# taster.net
KiCad netlist of a schematic drawn in EAGLE
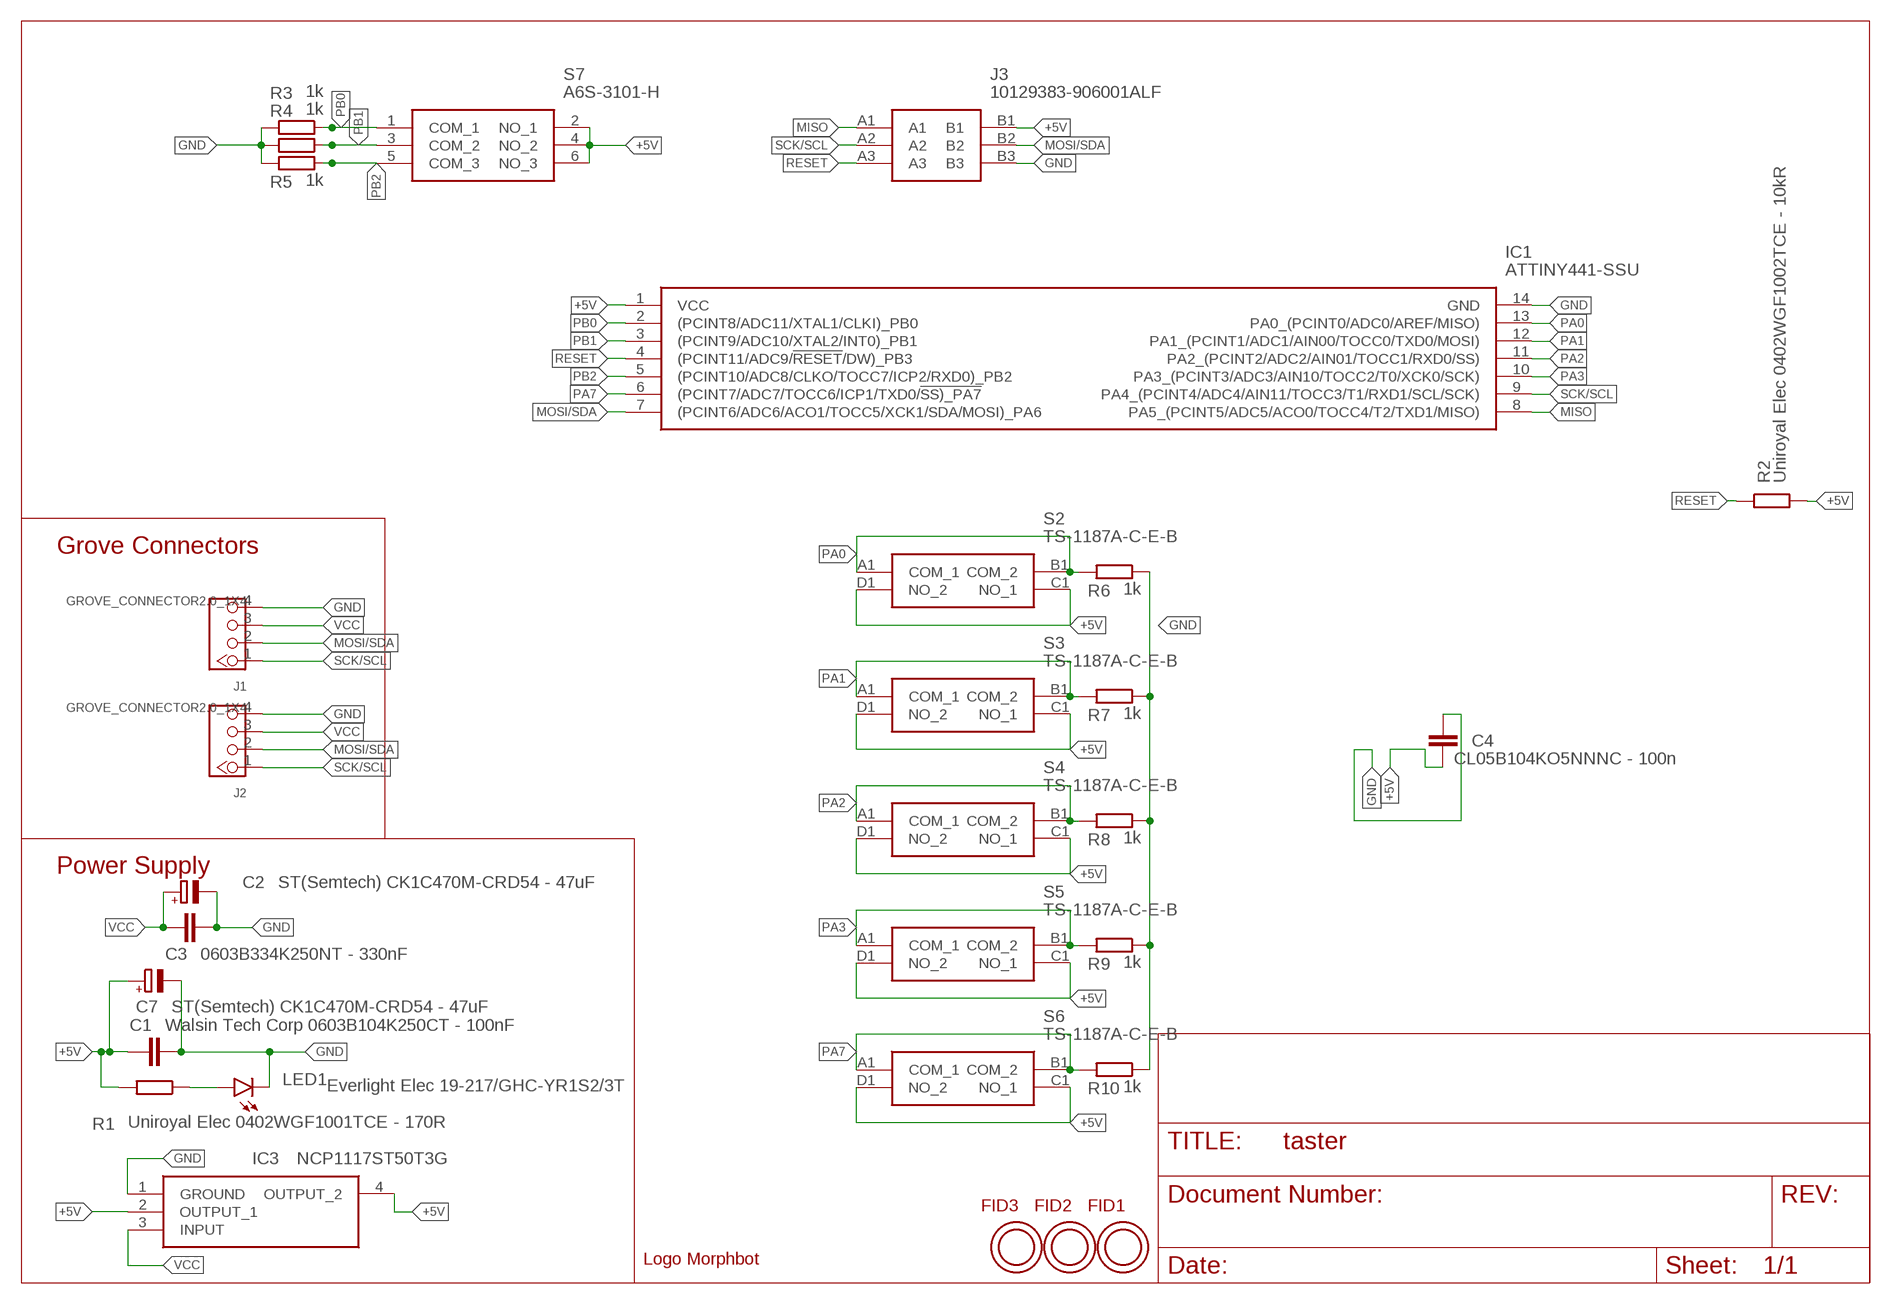
[diagram p0: schematic, sheet 1]

(export (version "E")
  (design (tool "Eeschema 10.0.6"))
  (components
    (comp (ref "C1")
      (value "Walsin Tech Corp 0603B104K250CT - 100nF")
      (footprint "eagle-import:C0603")
      (libsource (lib "eagle-import") (part "C-EUC0603"))
    )
    (comp (ref "C2")
      (value "ST(Semtech) CK1C470M-CRD54 - 47uF")
      (footprint "eagle-import:PANASONIC_C")
      (libsource (lib "eagle-import") (part "CPOL-EUC"))
    )
    (comp (ref "C3")
      (value "0603B334K250NT - 330nF")
      (footprint "eagle-import:C0603")
      (libsource (lib "eagle-import") (part "C-EUC0603"))
    )
    (comp (ref "C4")
      (value "CL05B104KO5NNNC - 100n")
      (footprint "eagle-import:C0402")
      (libsource (lib "eagle-import") (part "C-EUC0402"))
    )
    (comp (ref "C7")
      (value "ST(Semtech) CK1C470M-CRD54 - 47uF")
      (footprint "eagle-import:PANASONIC_C")
      (libsource (lib "eagle-import") (part "CPOL-EUC"))
    )
    (comp (ref "FID1")
      (value "OPEN-PNP-FIDUCIAL")
      (footprint "eagle-import:OPEN-PNP-FIDUCIAL")
      (libsource (lib "eagle-import") (part "OPEN-PNP-FIDUCIAL"))
    )
    (comp (ref "FID2")
      (value "OPEN-PNP-FIDUCIAL")
      (footprint "eagle-import:OPEN-PNP-FIDUCIAL")
      (libsource (lib "eagle-import") (part "OPEN-PNP-FIDUCIAL"))
    )
    (comp (ref "FID3")
      (value "OPEN-PNP-FIDUCIAL")
      (footprint "eagle-import:OPEN-PNP-FIDUCIAL")
      (libsource (lib "eagle-import") (part "OPEN-PNP-FIDUCIAL"))
    )
    (comp (ref "IC1")
      (value "ATTINY441-SSU")
      (footprint "eagle-import:SOIC127P600X175-14N")
      (fields (field (name "MOUSER_PART_NUMBER") "556-ATTINY441-SSU"))
      (libsource (lib "eagle-import") (part "ATTINY441-SSU"))
    )
    (comp (ref "IC3")
      (value "NCP1117ST50T3G")
      (footprint "eagle-import:SOT230P700X180-4N")
      (fields (field (name "MOUSER_PART_NUMBER") "863-NCP1117ST50T3G"))
      (libsource (lib "eagle-import") (part "NCP1117ST50T3G"))
    )
    (comp (ref "J1")
      (value "GROVE_CONNECTOR2.0_1X4")
      (footprint "eagle-import:2.0_1X4_STRAIGHT")
      (libsource (lib "eagle-import") (part "GROVE_CONNECTOR2.0_1X4"))
    )
    (comp (ref "J2")
      (value "GROVE_CONNECTOR2.0_1X4")
      (footprint "eagle-import:2.0_1X4_STRAIGHT")
      (libsource (lib "eagle-import") (part "GROVE_CONNECTOR2.0_1X4"))
    )
    (comp (ref "J3")
      (value "10129383-906001ALF")
      (footprint "eagle-import:10129383906001ALF")
      (fields (field (name "MOUSER_PART_NUMBER") "649-1012938390601ALF"))
      (libsource (lib "eagle-import") (part "10129383-906001ALF"))
    )
    (comp (ref "LED1")
      (value "Everlight Elec 19-217/GHC-YR1S2/3T")
      (footprint "eagle-import:CHIPLED_0603")
      (libsource (lib "eagle-import") (part "LEDCHIPLED_0603"))
    )
    (comp (ref "R1")
      (value "Uniroyal Elec 0402WGF1001TCE - 170R")
      (footprint "eagle-import:R0402")
      (libsource (lib "eagle-import") (part "R-EU_R0402"))
    )
    (comp (ref "R2")
      (value "Uniroyal Elec 0402WGF1002TCE - 10kR")
      (footprint "eagle-import:R0402")
      (libsource (lib "eagle-import") (part "R-EU_R0402"))
    )
    (comp (ref "R3")
      (value "1k")
      (footprint "eagle-import:R0402")
      (libsource (lib "eagle-import") (part "R-EU_R0402"))
    )
    (comp (ref "R4")
      (value "1k")
      (footprint "eagle-import:R0402")
      (libsource (lib "eagle-import") (part "R-EU_R0402"))
    )
    (comp (ref "R5")
      (value "1k")
      (footprint "eagle-import:R0402")
      (libsource (lib "eagle-import") (part "R-EU_R0402"))
    )
    (comp (ref "R6")
      (value "1k")
      (footprint "eagle-import:R0402")
      (libsource (lib "eagle-import") (part "R-EU_R0402"))
    )
    (comp (ref "R7")
      (value "1k")
      (footprint "eagle-import:R0402")
      (libsource (lib "eagle-import") (part "R-EU_R0402"))
    )
    (comp (ref "R8")
      (value "1k")
      (footprint "eagle-import:R0402")
      (libsource (lib "eagle-import") (part "R-EU_R0402"))
    )
    (comp (ref "R9")
      (value "1k")
      (footprint "eagle-import:R0402")
      (libsource (lib "eagle-import") (part "R-EU_R0402"))
    )
    (comp (ref "R10")
      (value "1k")
      (footprint "eagle-import:R0402")
      (libsource (lib "eagle-import") (part "R-EU_R0402"))
    )
    (comp (ref "S2")
      (value "TS-1187A-C-E-B")
      (footprint "eagle-import:TS1187ACEB")
      (fields (field (name "MOUSER_PART_NUMBER") "611-PTS526SK15SMR2L"))
      (libsource (lib "eagle-import") (part "TS-1187A-C-E-B"))
    )
    (comp (ref "S3")
      (value "TS-1187A-C-E-B")
      (footprint "eagle-import:TS1187ACEB")
      (fields (field (name "MOUSER_PART_NUMBER") "611-PTS526SK15SMR2L"))
      (libsource (lib "eagle-import") (part "TS-1187A-C-E-B"))
    )
    (comp (ref "S4")
      (value "TS-1187A-C-E-B")
      (footprint "eagle-import:TS1187ACEB")
      (fields (field (name "MOUSER_PART_NUMBER") "611-PTS526SK15SMR2L"))
      (libsource (lib "eagle-import") (part "TS-1187A-C-E-B"))
    )
    (comp (ref "S5")
      (value "TS-1187A-C-E-B")
      (footprint "eagle-import:TS1187ACEB")
      (fields (field (name "MOUSER_PART_NUMBER") "611-PTS526SK15SMR2L"))
      (libsource (lib "eagle-import") (part "TS-1187A-C-E-B"))
    )
    (comp (ref "S6")
      (value "TS-1187A-C-E-B")
      (footprint "eagle-import:TS1187ACEB")
      (fields (field (name "MOUSER_PART_NUMBER") "611-PTS526SK15SMR2L"))
      (libsource (lib "eagle-import") (part "TS-1187A-C-E-B"))
    )
    (comp (ref "S7")
      (value "A6S-3101-H")
      (footprint "eagle-import:A6S3104H")
      (fields (field (name "MOUSER_PART_NUMBER") "653-A6S-3101-H"))
      (libsource (lib "eagle-import") (part "A6S-3101-H"))
    )
    (comp (ref "U$1")
      (value "LOGO_MORPHBOT5MM")
      (footprint "eagle-import:LOGO_MORPHBOT")
      (libsource (lib "eagle-import") (part "LOGO_MORPHBOT5MM"))
    )
  )
  (nets
    (net (code "1") (name "+5V") (class "Default")
      (node (ref "C1") (pin "1") (pinfunction "1_1") (pintype "passive"))
      (node (ref "C4") (pin "1") (pinfunction "1_1") (pintype "passive"))
      (node (ref "C7") (pin "+") (pinfunction "+_+") (pintype "passive"))
      (node (ref "IC1") (pin "1") (pinfunction "VCC_1") (pintype "bidirectional"))
      (node (ref "IC3") (pin "2") (pinfunction "OUTPUT_1_2") (pintype "bidirectional"))
      (node (ref "IC3") (pin "4") (pinfunction "OUTPUT_2_4") (pintype "bidirectional"))
      (node (ref "J3") (pin "B1") (pinfunction "B1_B1") (pintype "bidirectional"))
      (node (ref "R1") (pin "2") (pinfunction "2_2") (pintype "passive"))
      (node (ref "R2") (pin "2") (pinfunction "2_2") (pintype "passive"))
      (node (ref "S2") (pin "C1") (pinfunction "NO_1_C1") (pintype "bidirectional"))
      (node (ref "S2") (pin "D1") (pinfunction "NO_2_D1") (pintype "bidirectional"))
      (node (ref "S3") (pin "C1") (pinfunction "NO_1_C1") (pintype "bidirectional"))
      (node (ref "S3") (pin "D1") (pinfunction "NO_2_D1") (pintype "bidirectional"))
      (node (ref "S4") (pin "C1") (pinfunction "NO_1_C1") (pintype "bidirectional"))
      (node (ref "S4") (pin "D1") (pinfunction "NO_2_D1") (pintype "bidirectional"))
      (node (ref "S5") (pin "C1") (pinfunction "NO_1_C1") (pintype "bidirectional"))
      (node (ref "S5") (pin "D1") (pinfunction "NO_2_D1") (pintype "bidirectional"))
      (node (ref "S6") (pin "C1") (pinfunction "NO_1_C1") (pintype "bidirectional"))
      (node (ref "S6") (pin "D1") (pinfunction "NO_2_D1") (pintype "bidirectional"))
      (node (ref "S7") (pin "2") (pinfunction "NO_1_2") (pintype "bidirectional"))
      (node (ref "S7") (pin "4") (pinfunction "NO_2_4") (pintype "bidirectional"))
      (node (ref "S7") (pin "6") (pinfunction "NO_3_6") (pintype "bidirectional"))
    )
    (net (code "2") (name "GND") (class "Default")
      (node (ref "C1") (pin "2") (pinfunction "2_2") (pintype "passive"))
      (node (ref "C2") (pin "-") (pinfunction "-_-") (pintype "passive"))
      (node (ref "C3") (pin "1") (pinfunction "1_1") (pintype "passive"))
      (node (ref "C4") (pin "2") (pinfunction "2_2") (pintype "passive"))
      (node (ref "C7") (pin "-") (pinfunction "-_-") (pintype "passive"))
      (node (ref "IC1") (pin "14") (pinfunction "GND_14") (pintype "bidirectional"))
      (node (ref "IC3") (pin "1") (pinfunction "GROUND_1") (pintype "bidirectional"))
      (node (ref "J1") (pin "4") (pinfunction "4_4") (pintype "bidirectional"))
      (node (ref "J2") (pin "4") (pinfunction "4_4") (pintype "bidirectional"))
      (node (ref "J3") (pin "B3") (pinfunction "B3_B3") (pintype "bidirectional"))
      (node (ref "LED1") (pin "C") (pinfunction "C_C") (pintype "passive"))
      (node (ref "R10") (pin "1") (pinfunction "1_1") (pintype "passive"))
      (node (ref "R3") (pin "2") (pinfunction "2_2") (pintype "passive"))
      (node (ref "R4") (pin "2") (pinfunction "2_2") (pintype "passive"))
      (node (ref "R5") (pin "2") (pinfunction "2_2") (pintype "passive"))
      (node (ref "R6") (pin "1") (pinfunction "1_1") (pintype "passive"))
      (node (ref "R7") (pin "1") (pinfunction "1_1") (pintype "passive"))
      (node (ref "R8") (pin "1") (pinfunction "1_1") (pintype "passive"))
      (node (ref "R9") (pin "1") (pinfunction "1_1") (pintype "passive"))
    )
    (net (code "3") (name "MISO") (class "Default")
      (node (ref "IC1") (pin "8") (pinfunction "PA5_(PCINT5/ADC5/ACO0/TOCC4/T2/TXD1/MISO)_8") (pintype "bidirectional"))
      (node (ref "J3") (pin "A1") (pinfunction "A1_A1") (pintype "bidirectional"))
    )
    (net (code "4") (name "MOSI{slash}SDA") (class "Default")
      (node (ref "IC1") (pin "7") (pinfunction "(PCINT6/ADC6/ACO1/TOCC5/XCK1/SDA/MOSI)_PA6_7") (pintype "bidirectional"))
      (node (ref "J1") (pin "2") (pinfunction "2_2") (pintype "bidirectional"))
      (node (ref "J2") (pin "2") (pinfunction "2_2") (pintype "bidirectional"))
      (node (ref "J3") (pin "B2") (pinfunction "B2_B2") (pintype "bidirectional"))
    )
    (net (code "5") (name "Net-(LED1-PadA)") (class "Default")
      (node (ref "LED1") (pin "A") (pinfunction "A_A") (pintype "passive"))
      (node (ref "R1") (pin "1") (pinfunction "1_1") (pintype "passive"))
    )
    (net (code "6") (name "PA0") (class "Default")
      (node (ref "IC1") (pin "13") (pinfunction "PA0_(PCINT0/ADC0/AREF/MISO)_13") (pintype "bidirectional"))
      (node (ref "R6") (pin "2") (pinfunction "2_2") (pintype "passive"))
      (node (ref "S2") (pin "A1") (pinfunction "COM_1_A1") (pintype "bidirectional"))
      (node (ref "S2") (pin "B1") (pinfunction "COM_2_B1") (pintype "bidirectional"))
    )
    (net (code "7") (name "PA1") (class "Default")
      (node (ref "IC1") (pin "12") (pinfunction "PA1_(PCINT1/ADC1/AIN00/TOCC0/TXD0/MOSI)_12") (pintype "bidirectional"))
      (node (ref "R7") (pin "2") (pinfunction "2_2") (pintype "passive"))
      (node (ref "S3") (pin "A1") (pinfunction "COM_1_A1") (pintype "bidirectional"))
      (node (ref "S3") (pin "B1") (pinfunction "COM_2_B1") (pintype "bidirectional"))
    )
    (net (code "8") (name "PA2") (class "Default")
      (node (ref "IC1") (pin "11") (pinfunction "PA2_(PCINT2/ADC2/AIN01/TOCC1/RXD0/SS)_11") (pintype "bidirectional"))
      (node (ref "R8") (pin "2") (pinfunction "2_2") (pintype "passive"))
      (node (ref "S4") (pin "A1") (pinfunction "COM_1_A1") (pintype "bidirectional"))
      (node (ref "S4") (pin "B1") (pinfunction "COM_2_B1") (pintype "bidirectional"))
    )
    (net (code "9") (name "PA3") (class "Default")
      (node (ref "IC1") (pin "10") (pinfunction "PA3_(PCINT3/ADC3/AIN10/TOCC2/T0/XCK0/SCK)_10") (pintype "bidirectional"))
      (node (ref "R9") (pin "2") (pinfunction "2_2") (pintype "passive"))
      (node (ref "S5") (pin "A1") (pinfunction "COM_1_A1") (pintype "bidirectional"))
      (node (ref "S5") (pin "B1") (pinfunction "COM_2_B1") (pintype "bidirectional"))
    )
    (net (code "10") (name "PA7") (class "Default")
      (node (ref "IC1") (pin "6") (pinfunction "(PCINT7/ADC7/TOCC6/ICP1/TXD0/~{SS})_PA7_6") (pintype "bidirectional"))
      (node (ref "R10") (pin "2") (pinfunction "2_2") (pintype "passive"))
      (node (ref "S6") (pin "A1") (pinfunction "COM_1_A1") (pintype "bidirectional"))
      (node (ref "S6") (pin "B1") (pinfunction "COM_2_B1") (pintype "bidirectional"))
    )
    (net (code "11") (name "PB0") (class "Default")
      (node (ref "IC1") (pin "2") (pinfunction "(PCINT8/ADC11/XTAL1/CLKI)_PB0_2") (pintype "bidirectional"))
      (node (ref "R3") (pin "1") (pinfunction "1_1") (pintype "passive"))
      (node (ref "S7") (pin "1") (pinfunction "COM_1_1") (pintype "bidirectional"))
    )
    (net (code "12") (name "PB1") (class "Default")
      (node (ref "IC1") (pin "3") (pinfunction "(PCINT9/ADC10/XTAL2/INT0)_PB1_3") (pintype "bidirectional"))
      (node (ref "R4") (pin "1") (pinfunction "1_1") (pintype "passive"))
      (node (ref "S7") (pin "3") (pinfunction "COM_2_3") (pintype "bidirectional"))
    )
    (net (code "13") (name "PB2") (class "Default")
      (node (ref "IC1") (pin "5") (pinfunction "(PCINT10/ADC8/CLKO/TOCC7/ICP2/RXD0)_PB2_5") (pintype "bidirectional"))
      (node (ref "R5") (pin "1") (pinfunction "1_1") (pintype "passive"))
      (node (ref "S7") (pin "5") (pinfunction "COM_3_5") (pintype "bidirectional"))
    )
    (net (code "14") (name "RESET") (class "Default")
      (node (ref "IC1") (pin "4") (pinfunction "(PCINT11/ADC9/~{RESET}/DW)_PB3_4") (pintype "bidirectional"))
      (node (ref "J3") (pin "A3") (pinfunction "A3_A3") (pintype "bidirectional"))
      (node (ref "R2") (pin "1") (pinfunction "1_1") (pintype "passive"))
    )
    (net (code "15") (name "SCK{slash}SCL") (class "Default")
      (node (ref "IC1") (pin "9") (pinfunction "PA4_(PCINT4/ADC4/AIN11/TOCC3/T1/RXD1/SCL/SCK)_9") (pintype "bidirectional"))
      (node (ref "J1") (pin "1") (pinfunction "1_1") (pintype "bidirectional"))
      (node (ref "J2") (pin "1") (pinfunction "1_1") (pintype "bidirectional"))
      (node (ref "J3") (pin "A2") (pinfunction "A2_A2") (pintype "bidirectional"))
    )
    (net (code "16") (name "VCC") (class "Default")
      (node (ref "C2") (pin "+") (pinfunction "+_+") (pintype "passive"))
      (node (ref "C3") (pin "2") (pinfunction "2_2") (pintype "passive"))
      (node (ref "IC3") (pin "3") (pinfunction "INPUT_3") (pintype "bidirectional"))
      (node (ref "J1") (pin "3") (pinfunction "3_3") (pintype "bidirectional"))
      (node (ref "J2") (pin "3") (pinfunction "3_3") (pintype "bidirectional"))
    )
  )
)
